# MCPICKUP.net
KiCad netlist of a schematic drawn in EasyEDA
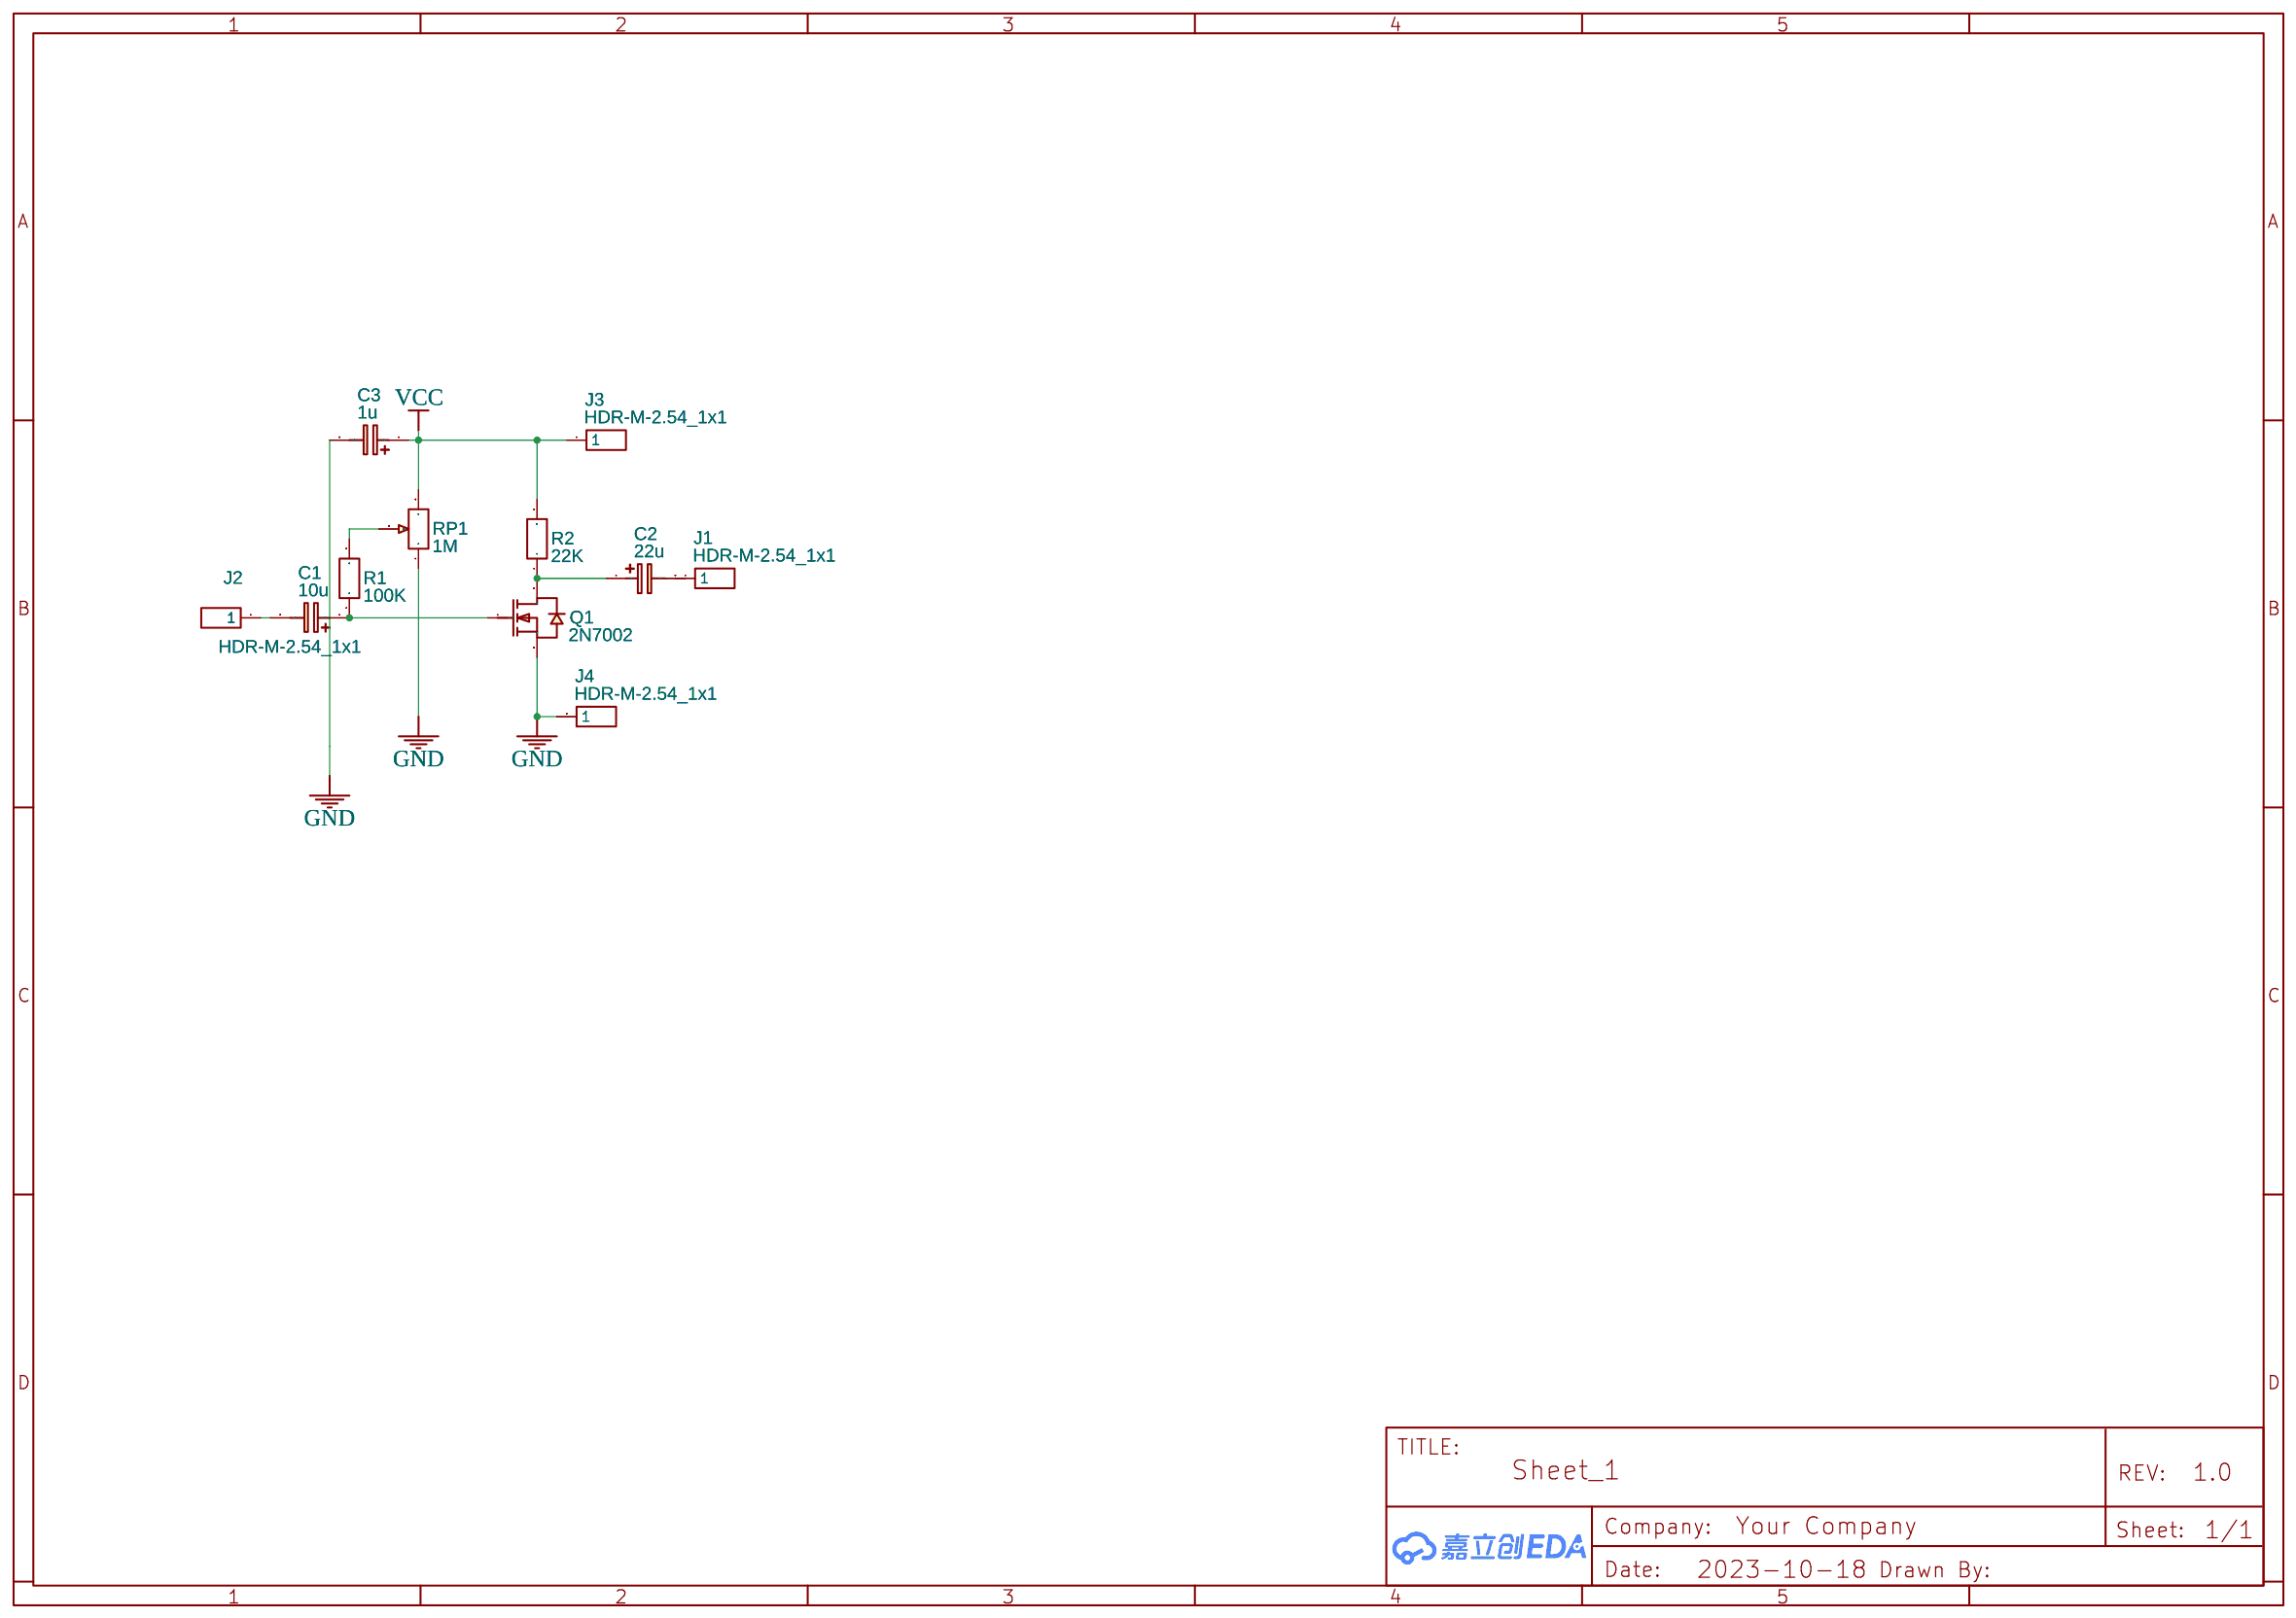
[diagram p0: schematic sheet]

(export (version "E")
  (design (tool "Eeschema 10.0.6"))
  (components
    (comp (ref "C1") (value "10u") (libsource (lib "") (part "C_Tan_SMD_A_EU")))
    (comp (ref "C2") (value "22u") (libsource (lib "") (part "C_Tan_SMD_A_EU_1")))
    (comp (ref "C3") (value "1u") (libsource (lib "") (part "C_Tan_SMD_A_EU_2")))
    (comp (ref "J1")
      (value "HDR-M-2.54_1x1")
      (fields (field (name "BOM_Supplier Part") "C81276"))
      (libsource (lib "") (part "HDR-M-2.54_1x1"))
    )
    (comp (ref "J2")
      (value "HDR-M-2.54_1x1")
      (fields (field (name "BOM_Supplier Part") "C81276"))
      (libsource (lib "") (part "HDR-M-2.54_1x1_1"))
    )
    (comp (ref "J3")
      (value "HDR-M-2.54_1x1")
      (fields (field (name "BOM_Supplier Part") "C81276"))
      (libsource (lib "") (part "HDR-M-2.54_1x1"))
    )
    (comp (ref "J4")
      (value "HDR-M-2.54_1x1")
      (fields (field (name "BOM_Supplier Part") "C81276"))
      (libsource (lib "") (part "HDR-M-2.54_1x1"))
    )
    (comp (ref "Q1")
      (value "2N7002")
      (fields (field (name "BOM_Manufacturer Part") "2N7002,215") (field (name "BOM_Supplier Part") "C65189"))
      (libsource (lib "") (part "2N7002"))
    )
    (comp (ref "R1") (value "100K") (libsource (lib "") (part "R_0603_EU")))
    (comp (ref "R2") (value "22K") (libsource (lib "") (part "R_0603_EU")))
    (comp (ref "RP1") (value "1M") (libsource (lib "") (part "R_3296W_EU")))
  )
  (nets
    (net (code "1") (name "GND") (class "Default")
      (node (ref "C3") (pin "2") (pinfunction "2_2") (pintype "unspecified"))
      (node (ref "J4") (pin "1") (pinfunction "1_1") (pintype "input"))
      (node (ref "Q1") (pin "2") (pinfunction "S_2") (pintype "unspecified"))
      (node (ref "RP1") (pin "1") (pinfunction "1_1") (pintype "input"))
    )
    (net (code "2") (name "Net-(C1-Pad2)") (class "Default")
      (node (ref "C1") (pin "2") (pinfunction "2_2") (pintype "unspecified"))
      (node (ref "J2") (pin "1") (pinfunction "1_1") (pintype "input"))
    )
    (net (code "3") (name "Net-(Q1-D)") (class "Default")
      (node (ref "C2") (pin "1") (pinfunction "1_1") (pintype "unspecified"))
      (node (ref "Q1") (pin "3") (pinfunction "D_3") (pintype "unspecified"))
      (node (ref "R2") (pin "1") (pinfunction "1_1") (pintype "unspecified"))
    )
    (net (code "4") (name "Net-(Q1-G)") (class "Default")
      (node (ref "C1") (pin "1") (pinfunction "1_1") (pintype "unspecified"))
      (node (ref "Q1") (pin "1") (pinfunction "G_1") (pintype "unspecified"))
      (node (ref "R1") (pin "1") (pinfunction "1_1") (pintype "unspecified"))
    )
    (net (code "5") (name "Net-(R1-Pad2)") (class "Default")
      (node (ref "R1") (pin "2") (pinfunction "2_2") (pintype "unspecified"))
      (node (ref "RP1") (pin "2") (pinfunction "2_2") (pintype "input"))
    )
    (net (code "6") (name "VCC") (class "Default")
      (node (ref "C3") (pin "1") (pinfunction "1_1") (pintype "unspecified"))
      (node (ref "J3") (pin "1") (pinfunction "1_1") (pintype "input"))
      (node (ref "R2") (pin "2") (pinfunction "2_2") (pintype "unspecified"))
      (node (ref "RP1") (pin "3") (pinfunction "3_3") (pintype "input"))
    )
    (net (code "7") (name "unconnected-(C2-Pad2)") (class "Default")
      (node (ref "C2") (pin "2") (pinfunction "2_2") (pintype "unspecified"))
    )
    (net (code "8") (name "unconnected-(J1-Pad1)") (class "Default")
      (node (ref "J1") (pin "1") (pinfunction "1_1") (pintype "input"))
    )
  )
)
